# Strvo_Tester_STM_renual_v1.net
KiCad netlist of a schematic drawn in EAGLE
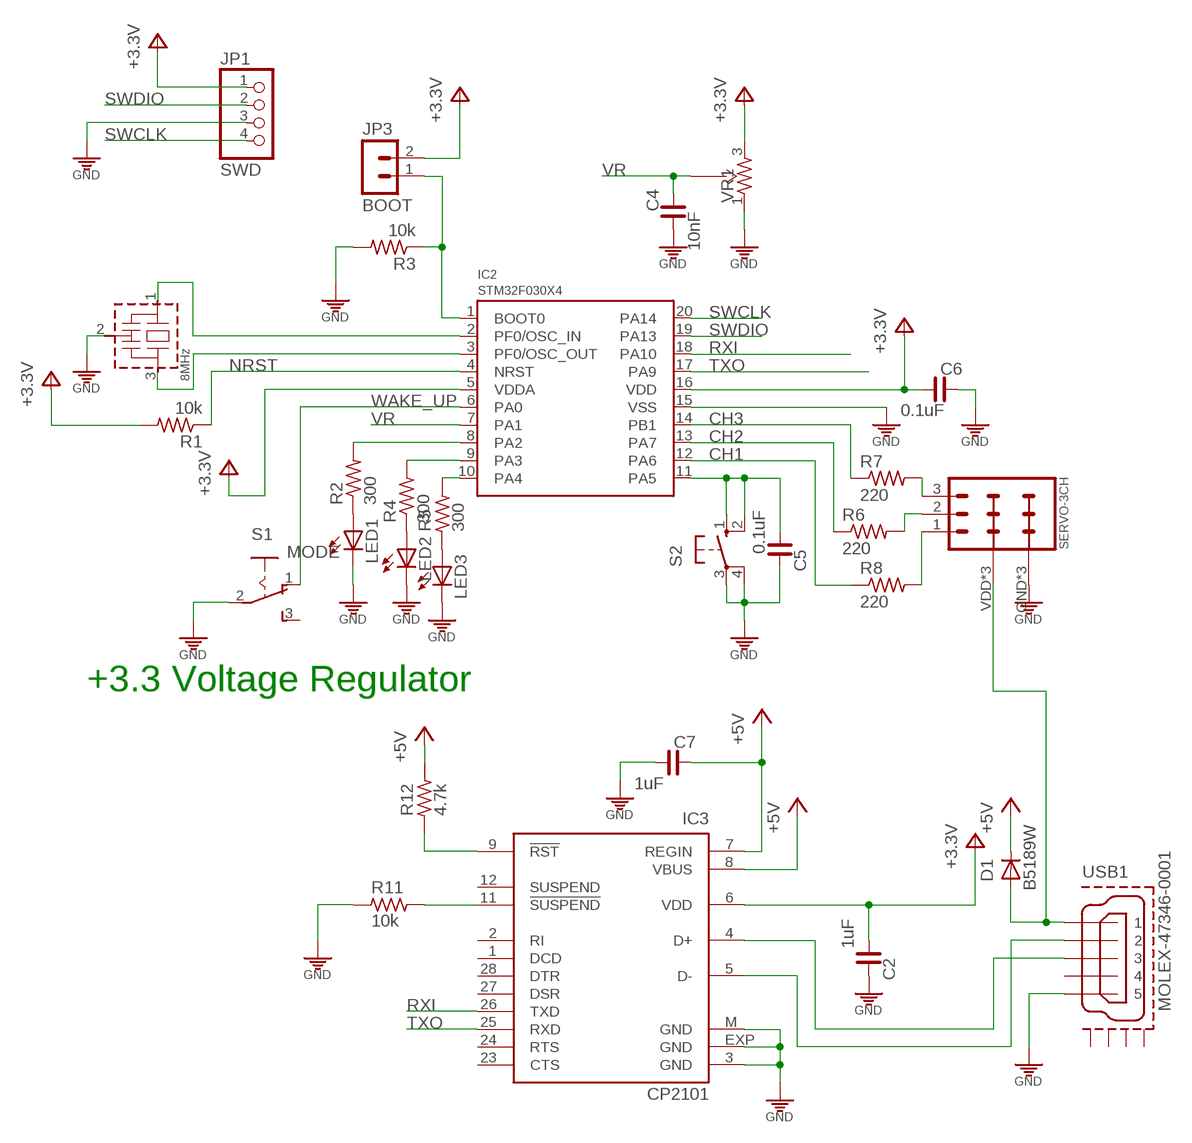
[diagram p0: schematic, sheet 1]

(export (version "E")
  (design (tool "Eeschema 10.0.6"))
  (components
    (comp (ref "C2")
      (value "1uF")
      (footprint "eagle-import:C0603")
      (libsource (lib "eagle-import") (part "C_0603"))
    )
    (comp (ref "C4")
      (value "10nF")
      (footprint "eagle-import:C0603")
      (libsource (lib "eagle-import") (part "C_0603"))
    )
    (comp (ref "C5")
      (value "0.1uF")
      (footprint "eagle-import:C0603")
      (libsource (lib "eagle-import") (part "C_0603"))
    )
    (comp (ref "C6")
      (value "0.1uF")
      (footprint "eagle-import:C0603")
      (libsource (lib "eagle-import") (part "C_0603"))
    )
    (comp (ref "C7")
      (value "1uF")
      (footprint "eagle-import:C0603")
      (libsource (lib "eagle-import") (part "C_0603"))
    )
    (comp (ref "D1")
      (value "B5189W")
      (footprint "eagle-import:SOD323")
      (libsource (lib "eagle-import") (part "B5189WN"))
    )
    (comp (ref "IC2")
      (value "STM32F030X4")
      (footprint "eagle-import:TSSOP20")
      (libsource (lib "eagle-import") (part "STM32F030X4"))
    )
    (comp (ref "IC3")
      (value "CP2101")
      (footprint "eagle-import:MLP28")
      (fields (field (name "MF") "FARNELL") (field (name "MPN") "CP2102-GM"))
      (libsource (lib "eagle-import") (part "CP2101"))
    )
    (comp (ref "JP1")
      (value "SWD")
      (footprint "eagle-import:1X04M")
      (libsource (lib "eagle-import") (part "PINHD-1X4M"))
    )
    (comp (ref "JP2")
      (value "SERVO-3CH")
      (footprint "eagle-import:SERVO-3CH1")
      (libsource (lib "eagle-import") (part "SERVO-3CH"))
    )
    (comp (ref "JP3")
      (value "BOOT")
      (footprint "eagle-import:MA02-MINI")
      (libsource (lib "eagle-import") (part "MA021.25"))
    )
    (comp (ref "LED1")
      (value "LED3MM")
      (footprint "eagle-import:LED3MM")
      (libsource (lib "eagle-import") (part "LED3MM"))
    )
    (comp (ref "LED2")
      (value "LED3MM")
      (footprint "eagle-import:LED3MM")
      (libsource (lib "eagle-import") (part "LED3MM"))
    )
    (comp (ref "LED3")
      (value "LED3MM")
      (footprint "eagle-import:LED3MM")
      (libsource (lib "eagle-import") (part "LED3MM"))
    )
    (comp (ref "Q1")
      (value "8MHz")
      (footprint "eagle-import:CSTLA_X")
      (libsource (lib "eagle-import") (part "X-TAL-SMALLCSTCE16M00V53"))
    )
    (comp (ref "R1")
      (value "10k")
      (footprint "eagle-import:R0603")
      (libsource (lib "eagle-import") (part "R-US_R1608"))
    )
    (comp (ref "R2")
      (value "300")
      (footprint "eagle-import:R0603")
      (libsource (lib "eagle-import") (part "R-US_R1608"))
    )
    (comp (ref "R3")
      (value "10k")
      (footprint "eagle-import:R0603")
      (libsource (lib "eagle-import") (part "R-US_R1608"))
    )
    (comp (ref "R4")
      (value "300")
      (footprint "eagle-import:R0603")
      (libsource (lib "eagle-import") (part "R-US_R1608"))
    )
    (comp (ref "R5")
      (value "300")
      (footprint "eagle-import:R0603")
      (libsource (lib "eagle-import") (part "R_0603"))
    )
    (comp (ref "R6")
      (value "220")
      (footprint "eagle-import:R0603")
      (libsource (lib "eagle-import") (part "R-US_R1608"))
    )
    (comp (ref "R7")
      (value "220")
      (footprint "eagle-import:R0603")
      (libsource (lib "eagle-import") (part "R-US_R1608"))
    )
    (comp (ref "R8")
      (value "220")
      (footprint "eagle-import:R0603")
      (libsource (lib "eagle-import") (part "R-US_R1608"))
    )
    (comp (ref "R11")
      (value "10k")
      (footprint "eagle-import:R0603")
      (libsource (lib "eagle-import") (part "R_0603"))
    )
    (comp (ref "R12")
      (value "4.7k")
      (footprint "eagle-import:R0603")
      (libsource (lib "eagle-import") (part "R_0603"))
    )
    (comp (ref "S1")
      (value "MODE")
      (footprint "eagle-import:255SB")
      (libsource (lib "eagle-import") (part "IMMS"))
    )
    (comp (ref "S2")
      (value "10-XX")
      (footprint "eagle-import:B3F-10XX")
      (fields (field (name "MPN") "B3F-1000"))
      (libsource (lib "eagle-import") (part "10-XX"))
    )
    (comp (ref "USB1")
      (value "MOLEX-47346-0001")
      (footprint "eagle-import:MOLEX-47364-0001")
      (libsource (lib "eagle-import") (part "MOLEX-47346-0001"))
    )
    (comp (ref "VR1")
      (value "R-TRIMMER-SMDPTV")
      (footprint "eagle-import:PTV09")
      (libsource (lib "eagle-import") (part "R-TRIMMER-SMDPTV"))
    )
  )
  (nets
    (net (code "1") (name "+3V3") (class "Default")
      (node (ref "C2") (pin "2") (pinfunction "2_2") (pintype "passive"))
      (node (ref "C6") (pin "2") (pinfunction "2_2") (pintype "passive"))
      (node (ref "IC2") (pin "16") (pinfunction "VDD_16") (pintype "power_in"))
      (node (ref "IC2") (pin "5") (pinfunction "VDDA_5") (pintype "power_in"))
      (node (ref "IC3") (pin "6") (pinfunction "VDD_6") (pintype "power_in"))
      (node (ref "JP1") (pin "1") (pinfunction "1_1") (pintype "passive"))
      (node (ref "JP3") (pin "2") (pinfunction "2_2") (pintype "passive"))
      (node (ref "R1") (pin "2") (pinfunction "2_2") (pintype "passive"))
      (node (ref "VR1") (pin "3") (pinfunction "3_3") (pintype "passive"))
    )
    (net (code "2") (name "+5V") (class "Default")
      (node (ref "C7") (pin "1") (pinfunction "1_1") (pintype "passive"))
      (node (ref "D1") (pin "C") (pinfunction "C_C") (pintype "passive"))
      (node (ref "IC3") (pin "7") (pinfunction "REGIN_7") (pintype "passive"))
      (node (ref "IC3") (pin "8") (pinfunction "VBUS_8") (pintype "input"))
      (node (ref "R12") (pin "2") (pinfunction "2_2") (pintype "passive"))
    )
    (net (code "3") (name "/CH1") (class "Default")
      (node (ref "IC2") (pin "12") (pinfunction "PA6_12") (pintype "bidirectional"))
      (node (ref "R8") (pin "1") (pinfunction "1_1") (pintype "passive"))
    )
    (net (code "4") (name "/CH2") (class "Default")
      (node (ref "IC2") (pin "13") (pinfunction "PA7_13") (pintype "bidirectional"))
      (node (ref "R6") (pin "1") (pinfunction "1_1") (pintype "passive"))
    )
    (net (code "5") (name "/CH3") (class "Default")
      (node (ref "IC2") (pin "14") (pinfunction "PB1_14") (pintype "bidirectional"))
      (node (ref "R7") (pin "1") (pinfunction "1_1") (pintype "passive"))
    )
    (net (code "6") (name "/NRST") (class "Default")
      (node (ref "IC2") (pin "4") (pinfunction "NRST_4") (pintype "bidirectional"))
      (node (ref "R1") (pin "1") (pinfunction "1_1") (pintype "passive"))
    )
    (net (code "7") (name "/RXI") (class "Default")
      (node (ref "IC2") (pin "18") (pinfunction "PA10_18") (pintype "bidirectional"))
      (node (ref "IC3") (pin "26") (pinfunction "TXD_26") (pintype "output"))
    )
    (net (code "8") (name "/SWCLK") (class "Default")
      (node (ref "IC2") (pin "20") (pinfunction "PA14_20") (pintype "bidirectional"))
      (node (ref "JP1") (pin "4") (pinfunction "4_4") (pintype "passive"))
    )
    (net (code "9") (name "/SWDIO") (class "Default")
      (node (ref "IC2") (pin "19") (pinfunction "PA13_19") (pintype "bidirectional"))
      (node (ref "JP1") (pin "2") (pinfunction "2_2") (pintype "passive"))
    )
    (net (code "10") (name "/TXO") (class "Default")
      (node (ref "IC2") (pin "17") (pinfunction "PA9_17") (pintype "bidirectional"))
      (node (ref "IC3") (pin "25") (pinfunction "RXD_25") (pintype "input"))
    )
    (net (code "11") (name "/VR") (class "Default")
      (node (ref "C4") (pin "1") (pinfunction "1_1") (pintype "passive"))
      (node (ref "IC2") (pin "7") (pinfunction "PA1_7") (pintype "bidirectional"))
      (node (ref "VR1") (pin "2") (pinfunction "2_2") (pintype "passive"))
    )
    (net (code "12") (name "/WAKE_UP") (class "Default")
      (node (ref "IC2") (pin "6") (pinfunction "PA0_6") (pintype "bidirectional"))
      (node (ref "S1") (pin "1") (pinfunction "O_1") (pintype "passive"))
    )
    (net (code "13") (name "GND") (class "Default")
      (node (ref "C2") (pin "1") (pinfunction "1_1") (pintype "passive"))
      (node (ref "C4") (pin "2") (pinfunction "2_2") (pintype "passive"))
      (node (ref "C5") (pin "1") (pinfunction "1_1") (pintype "passive"))
      (node (ref "C6") (pin "1") (pinfunction "1_1") (pintype "passive"))
      (node (ref "C7") (pin "2") (pinfunction "2_2") (pintype "passive"))
      (node (ref "IC2") (pin "15") (pinfunction "VSS_15") (pintype "power_in"))
      (node (ref "IC3") (pin "3") (pinfunction "GND_3") (pintype "power_in"))
      (node (ref "IC3") (pin "EXP") (pinfunction "GND_EXP") (pintype "power_in"))
      (node (ref "IC3") (pin "M") (pinfunction "GND_M") (pintype "power_in"))
      (node (ref "JP1") (pin "3") (pinfunction "3_3") (pintype "passive"))
      (node (ref "JP2") (pin "GND") (pinfunction "GND_GND") (pintype "passive"))
      (node (ref "JP2") (pin "GND@1") (pinfunction "GND_GND@1") (pintype "passive"))
      (node (ref "JP2") (pin "GND@2") (pinfunction "GND_GND@2") (pintype "passive"))
      (node (ref "LED1") (pin "K") (pinfunction "C_K") (pintype "passive"))
      (node (ref "LED2") (pin "K") (pinfunction "C_K") (pintype "passive"))
      (node (ref "LED3") (pin "K") (pinfunction "C_K") (pintype "passive"))
      (node (ref "Q1") (pin "2") (pinfunction "GND_2") (pintype "power_in"))
      (node (ref "R11") (pin "1") (pinfunction "1_1") (pintype "passive"))
      (node (ref "R3") (pin "2") (pinfunction "2_2") (pintype "passive"))
      (node (ref "S1") (pin "2") (pinfunction "P_2") (pintype "passive"))
      (node (ref "S2") (pin "3") (pinfunction "P_3") (pintype "passive"))
      (node (ref "S2") (pin "4") (pinfunction "P1_4") (pintype "passive"))
      (node (ref "USB1") (pin "5") (pinfunction "5_5") (pintype "input"))
      (node (ref "VR1") (pin "1") (pinfunction "1_1") (pintype "passive"))
    )
    (net (code "14") (name "Net-(D1-PadA)") (class "Default")
      (node (ref "D1") (pin "A") (pinfunction "A_A") (pintype "passive"))
      (node (ref "JP2") (pin "VDD") (pinfunction "+5V_VDD") (pintype "passive"))
      (node (ref "JP2") (pin "VDD@1") (pinfunction "+5V_VDD@1") (pintype "passive"))
      (node (ref "JP2") (pin "VDD@2") (pinfunction "+5V_VDD@2") (pintype "passive"))
      (node (ref "USB1") (pin "1") (pinfunction "1_1") (pintype "input"))
    )
    (net (code "15") (name "Net-(IC2-BOOT0)") (class "Default")
      (node (ref "IC2") (pin "1") (pinfunction "BOOT0_1") (pintype "bidirectional"))
      (node (ref "JP3") (pin "1") (pinfunction "1_1") (pintype "passive"))
      (node (ref "R3") (pin "1") (pinfunction "1_1") (pintype "passive"))
    )
    (net (code "16") (name "Net-(IC2-PA2)") (class "Default")
      (node (ref "IC2") (pin "8") (pinfunction "PA2_8") (pintype "bidirectional"))
      (node (ref "R2") (pin "2") (pinfunction "2_2") (pintype "passive"))
    )
    (net (code "17") (name "Net-(IC2-PA3)") (class "Default")
      (node (ref "IC2") (pin "9") (pinfunction "PA3_9") (pintype "bidirectional"))
      (node (ref "R4") (pin "2") (pinfunction "2_2") (pintype "passive"))
    )
    (net (code "18") (name "Net-(IC2-PA4)") (class "Default")
      (node (ref "IC2") (pin "10") (pinfunction "PA4_10") (pintype "bidirectional"))
      (node (ref "R5") (pin "2") (pinfunction "2_2") (pintype "passive"))
    )
    (net (code "19") (name "Net-(IC2-PA5)") (class "Default")
      (node (ref "C5") (pin "2") (pinfunction "2_2") (pintype "passive"))
      (node (ref "IC2") (pin "11") (pinfunction "PA5_11") (pintype "bidirectional"))
      (node (ref "S2") (pin "1") (pinfunction "S_1") (pintype "passive"))
      (node (ref "S2") (pin "2") (pinfunction "S1_2") (pintype "passive"))
    )
    (net (code "20") (name "Net-(IC2-PF0{slash}OSC_IN)") (class "Default")
      (node (ref "IC2") (pin "2") (pinfunction "PF0/OSC_IN_2") (pintype "bidirectional"))
      (node (ref "Q1") (pin "1") (pinfunction "IN_1") (pintype "output"))
    )
    (net (code "21") (name "Net-(IC2-PF0{slash}OSC_OUT)") (class "Default")
      (node (ref "IC2") (pin "3") (pinfunction "PF0/OSC_OUT_3") (pintype "bidirectional"))
      (node (ref "Q1") (pin "3") (pinfunction "OUT_3") (pintype "input"))
    )
    (net (code "22") (name "Net-(IC3-D+)") (class "Default")
      (node (ref "IC3") (pin "4") (pinfunction "D+_4") (pintype "bidirectional"))
      (node (ref "USB1") (pin "3") (pinfunction "3_3") (pintype "input"))
    )
    (net (code "23") (name "Net-(IC3-D-)") (class "Default")
      (node (ref "IC3") (pin "5") (pinfunction "D-_5") (pintype "bidirectional"))
      (node (ref "USB1") (pin "2") (pinfunction "2_2") (pintype "input"))
    )
    (net (code "24") (name "Net-(IC3-~{RST})") (class "Default")
      (node (ref "IC3") (pin "9") (pinfunction "~{RST}_9") (pintype "bidirectional"))
      (node (ref "R12") (pin "1") (pinfunction "1_1") (pintype "passive"))
    )
    (net (code "25") (name "Net-(IC3-~{SUSPEND})") (class "Default")
      (node (ref "IC3") (pin "11") (pinfunction "~{SUSPEND}_11") (pintype "output"))
      (node (ref "R11") (pin "2") (pinfunction "2_2") (pintype "passive"))
    )
    (net (code "26") (name "Net-(JP2-Pad1)") (class "Default")
      (node (ref "JP2") (pin "1") (pinfunction "1_1") (pintype "passive"))
      (node (ref "R8") (pin "2") (pinfunction "2_2") (pintype "passive"))
    )
    (net (code "27") (name "Net-(JP2-Pad2)") (class "Default")
      (node (ref "JP2") (pin "2") (pinfunction "2_2") (pintype "passive"))
      (node (ref "R6") (pin "2") (pinfunction "2_2") (pintype "passive"))
    )
    (net (code "28") (name "Net-(JP2-Pad3)") (class "Default")
      (node (ref "JP2") (pin "3") (pinfunction "3_3") (pintype "passive"))
      (node (ref "R7") (pin "2") (pinfunction "2_2") (pintype "passive"))
    )
    (net (code "29") (name "Net-(LED1-PadA)") (class "Default")
      (node (ref "LED1") (pin "A") (pinfunction "A_A") (pintype "passive"))
      (node (ref "R2") (pin "1") (pinfunction "1_1") (pintype "passive"))
    )
    (net (code "30") (name "Net-(LED2-PadA)") (class "Default")
      (node (ref "LED2") (pin "A") (pinfunction "A_A") (pintype "passive"))
      (node (ref "R4") (pin "1") (pinfunction "1_1") (pintype "passive"))
    )
    (net (code "31") (name "Net-(LED3-PadA)") (class "Default")
      (node (ref "LED3") (pin "A") (pinfunction "A_A") (pintype "passive"))
      (node (ref "R5") (pin "1") (pinfunction "1_1") (pintype "passive"))
    )
    (net (code "32") (name "unconnected-(IC3-CTS-Pad23)") (class "Default")
      (node (ref "IC3") (pin "23") (pinfunction "CTS_23") (pintype "input"))
    )
    (net (code "33") (name "unconnected-(IC3-DCD-Pad1)") (class "Default")
      (node (ref "IC3") (pin "1") (pinfunction "DCD_1") (pintype "input"))
    )
    (net (code "34") (name "unconnected-(IC3-DSR-Pad27)") (class "Default")
      (node (ref "IC3") (pin "27") (pinfunction "DSR_27") (pintype "input"))
    )
    (net (code "35") (name "unconnected-(IC3-DTR-Pad28)") (class "Default")
      (node (ref "IC3") (pin "28") (pinfunction "DTR_28") (pintype "output"))
    )
    (net (code "36") (name "unconnected-(IC3-RI-Pad2)") (class "Default")
      (node (ref "IC3") (pin "2") (pinfunction "RI_2") (pintype "input"))
    )
    (net (code "37") (name "unconnected-(IC3-RTS-Pad24)") (class "Default")
      (node (ref "IC3") (pin "24") (pinfunction "RTS_24") (pintype "output"))
    )
    (net (code "38") (name "unconnected-(IC3-SUSPEND-Pad12)") (class "Default")
      (node (ref "IC3") (pin "12") (pinfunction "SUSPEND_12") (pintype "output"))
    )
    (net (code "39") (name "unconnected-(S1-S-Pad3)") (class "Default")
      (node (ref "S1") (pin "3") (pinfunction "S_3") (pintype "passive"))
    )
    (net (code "40") (name "unconnected-(USB1-Pad4)") (class "Default")
      (node (ref "USB1") (pin "4") (pinfunction "4_4") (pintype "input"))
    )
    (net (code "41") (name "unconnected-(USB1-PadGND1)") (class "Default")
      (node (ref "USB1") (pin "GND1") (pinfunction "GND1_GND1") (pintype "bidirectional"))
    )
    (net (code "42") (name "unconnected-(USB1-PadGND2)") (class "Default")
      (node (ref "USB1") (pin "GND2") (pinfunction "GND2_GND2") (pintype "bidirectional"))
    )
    (net (code "43") (name "unconnected-(USB1-PadGND3)") (class "Default")
      (node (ref "USB1") (pin "GND3") (pinfunction "GND3_GND3") (pintype "bidirectional"))
    )
    (net (code "44") (name "unconnected-(USB1-PadGND4)") (class "Default")
      (node (ref "USB1") (pin "GND4") (pinfunction "GND4_GND4") (pintype "bidirectional"))
    )
  )
)
